# SenseLora_Soil_Moisture_V1_0.net
KiCad netlist of a schematic drawn in EAGLE
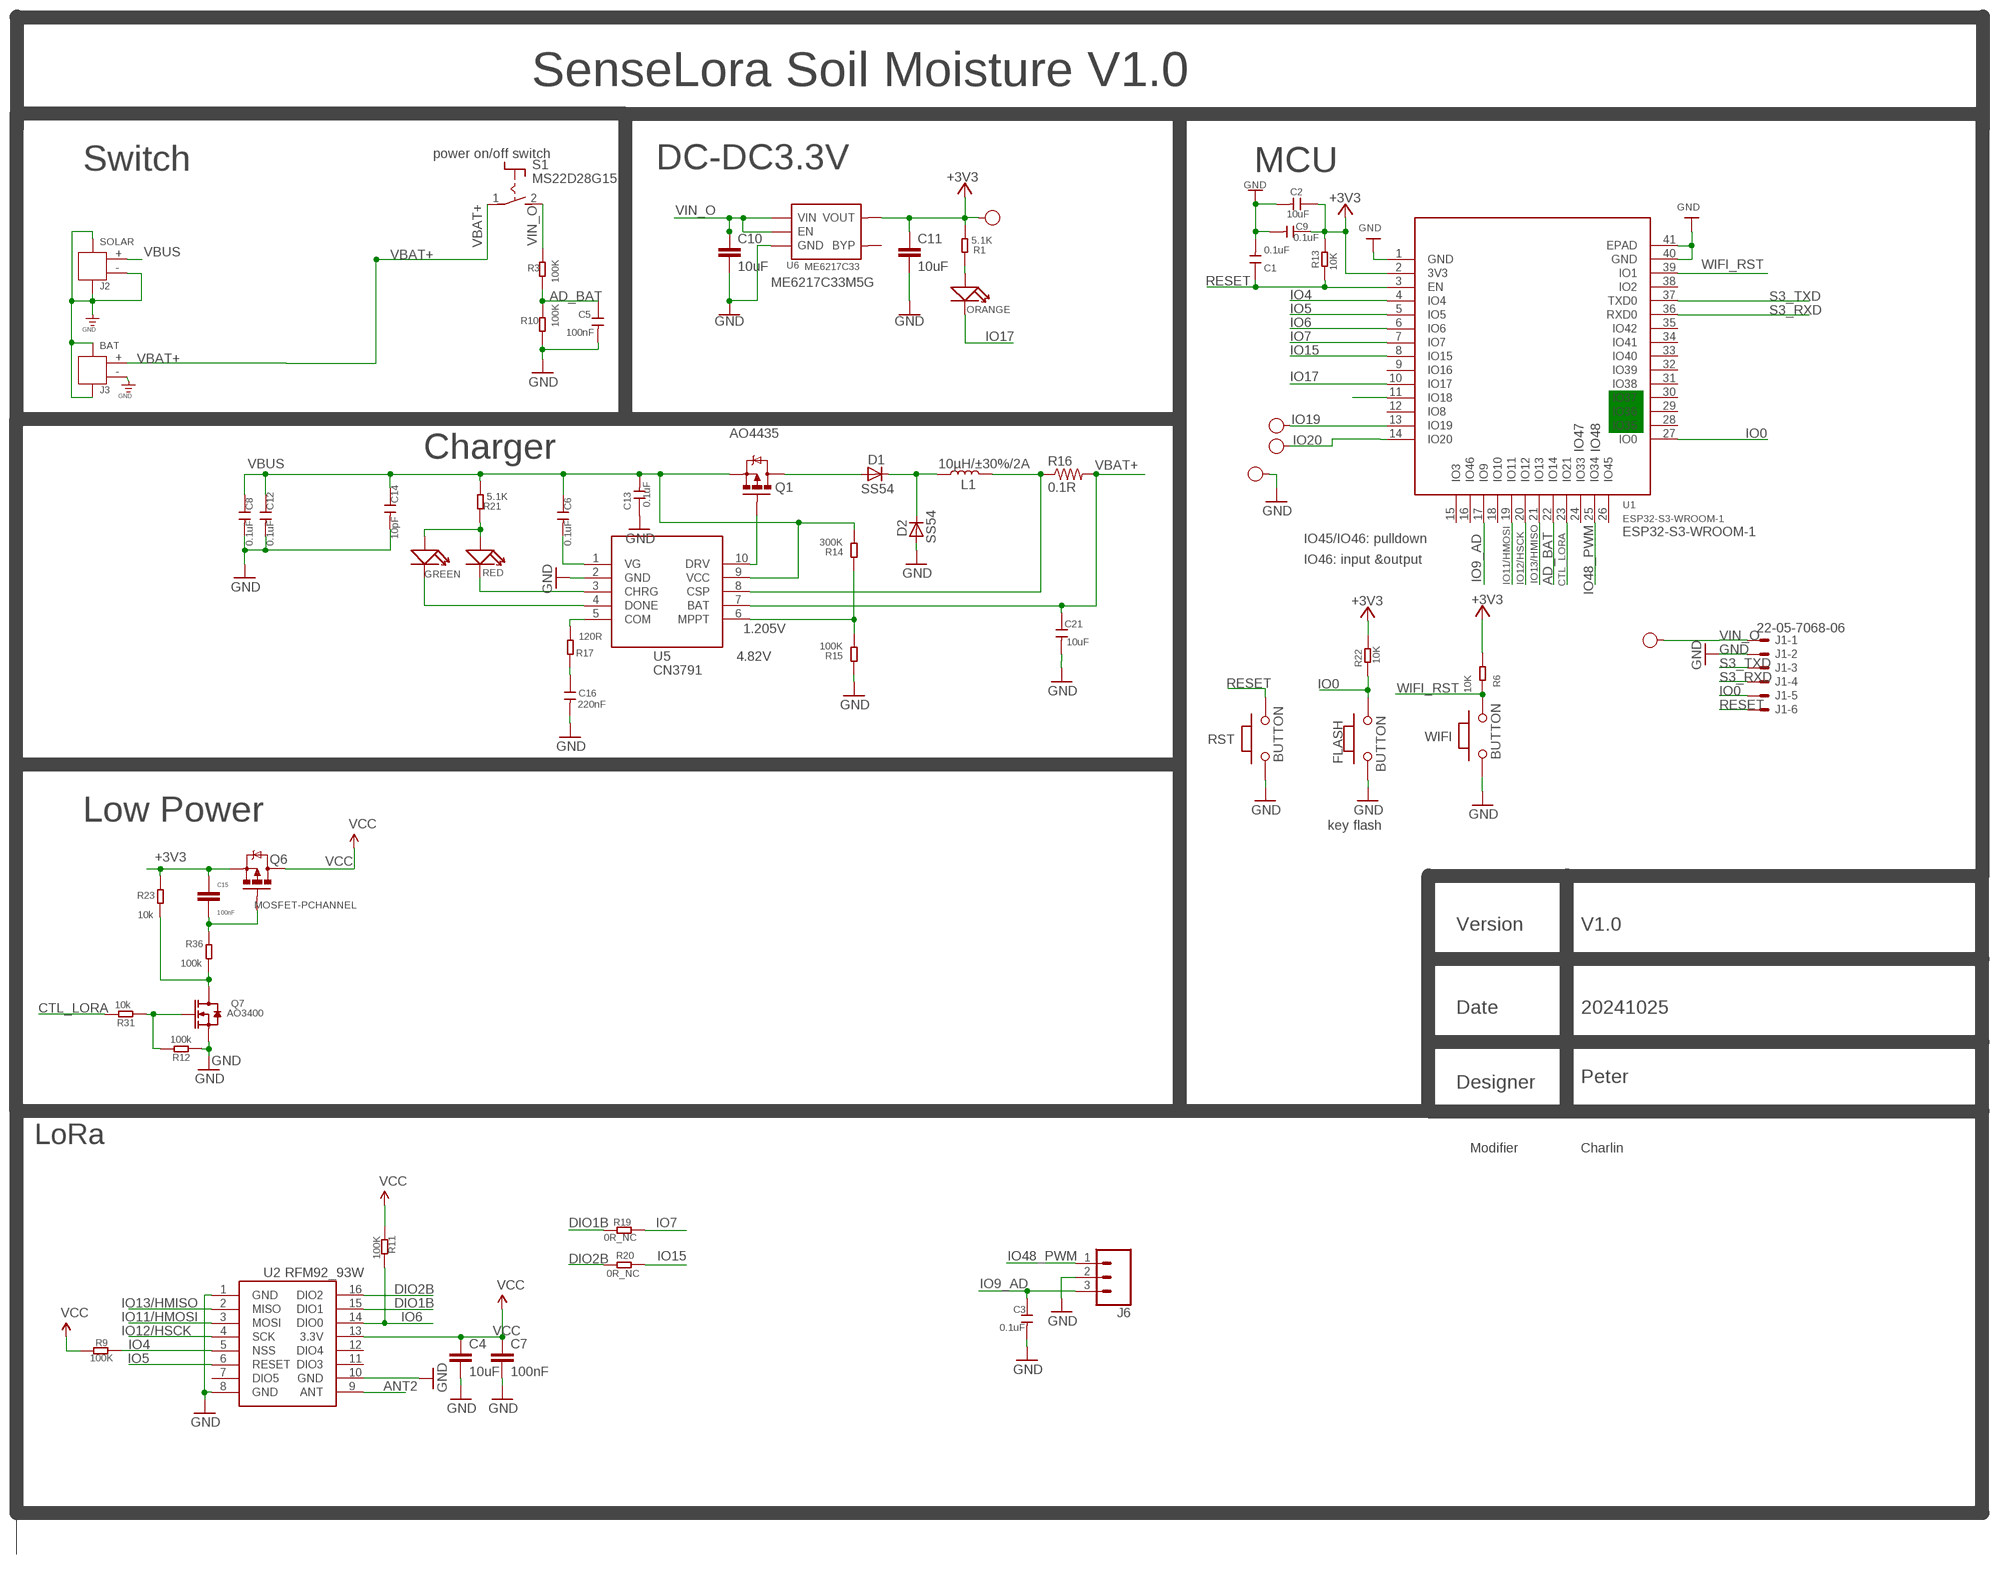
[diagram p0: schematic, sheet 1]

(export (version "E")
  (design (tool "Eeschema 10.0.6"))
  (components
    (comp (ref "3V3")
      (value "TEST-POINT'4545'")
      (footprint "eagle-import:TP-D45MIL")
      (fields (field (name "PARTNO") "DNP") (field (name "PARTNO_1") "DNP"))
      (libsource (lib "eagle-import") (part "TEST-POINT'4545'"))
    )
    (comp (ref "C1")
      (value "0.1uF")
      (footprint "eagle-import:DISCRETE_C0603")
      (libsource (lib "eagle-import") (part "DISCRETE_C-0603"))
    )
    (comp (ref "C2")
      (value "10uF")
      (footprint "eagle-import:DISCRETE_C0603")
      (libsource (lib "eagle-import") (part "DISCRETE_C-0603"))
    )
    (comp (ref "C3")
      (value "0.1uF")
      (footprint "eagle-import:DISCRETE_C0603")
      (libsource (lib "eagle-import") (part "DISCRETE_C-0603"))
    )
    (comp (ref "C4")
      (value "10uF")
      (footprint "eagle-import:C0603")
      (libsource (lib "eagle-import") (part "C0603"))
    )
    (comp (ref "C5")
      (value "100nF")
      (footprint "eagle-import:C0603")
      (libsource (lib "eagle-import") (part "CAP-0603"))
    )
    (comp (ref "C6")
      (value "0.1uF")
      (footprint "eagle-import:DISCRETE_C0603")
      (libsource (lib "eagle-import") (part "DISCRETE_C-0603"))
    )
    (comp (ref "C7")
      (value "100nF")
      (footprint "eagle-import:C0603")
      (libsource (lib "eagle-import") (part "C0603"))
    )
    (comp (ref "C8")
      (value "0.1uF")
      (footprint "eagle-import:DISCRETE_C0603")
      (libsource (lib "eagle-import") (part "DISCRETE_C-0603"))
    )
    (comp (ref "C9")
      (value "0.1uF")
      (footprint "eagle-import:DISCRETE_C0603")
      (libsource (lib "eagle-import") (part "DISCRETE_C-0603"))
    )
    (comp (ref "C10")
      (value "10uF")
      (footprint "eagle-import:C0603")
      (libsource (lib "eagle-import") (part "C0603"))
    )
    (comp (ref "C11")
      (value "10uF")
      (footprint "eagle-import:C0603")
      (libsource (lib "eagle-import") (part "C0603"))
    )
    (comp (ref "C12")
      (value "0.1uF")
      (footprint "eagle-import:DISCRETE_C0603")
      (libsource (lib "eagle-import") (part "DISCRETE_C-0603"))
    )
    (comp (ref "C13")
      (value "0.1uF")
      (footprint "eagle-import:DISCRETE_C0603")
      (libsource (lib "eagle-import") (part "DISCRETE_C-0603"))
    )
    (comp (ref "C14")
      (value "10pF")
      (footprint "eagle-import:DISCRETE_C0603")
      (libsource (lib "eagle-import") (part "DISCRETE_C-0603"))
    )
    (comp (ref "C15")
      (value "100nF")
      (footprint "eagle-import:C0603")
      (libsource (lib "eagle-import") (part "C0603"))
    )
    (comp (ref "C16")
      (value "220nF")
      (footprint "eagle-import:DISCRETE_C0603")
      (libsource (lib "eagle-import") (part "DISCRETE_C-0603"))
    )
    (comp (ref "C21")
      (value "10uF")
      (footprint "eagle-import:DISCRETE_C0603")
      (libsource (lib "eagle-import") (part "DISCRETE_C-0603"))
    )
    (comp (ref "CHRG")
      (value "RED")
      (footprint "eagle-import:LED-0603")
      (libsource (lib "eagle-import") (part "LED'0603'"))
    )
    (comp (ref "D+")
      (value "TEST-POINT'4545'")
      (footprint "eagle-import:TP-D45MIL")
      (fields (field (name "PARTNO") "DNP") (field (name "PARTNO_1") "DNP"))
      (libsource (lib "eagle-import") (part "TEST-POINT'4545'"))
    )
    (comp (ref "D-")
      (value "TEST-POINT'4545'")
      (footprint "eagle-import:TP-D45MIL")
      (fields (field (name "PARTNO") "DNP") (field (name "PARTNO_1") "DNP"))
      (libsource (lib "eagle-import") (part "TEST-POINT'4545'"))
    )
    (comp (ref "D1")
      (value "SS54")
      (footprint "eagle-import:DO-214AC")
      (libsource (lib "eagle-import") (part "DIODE-DO-214AC"))
    )
    (comp (ref "D2")
      (value "SS54")
      (footprint "eagle-import:DO-214AC")
      (libsource (lib "eagle-import") (part "DIODE-DO-214AC"))
    )
    (comp (ref "DONE")
      (value "GREEN")
      (footprint "eagle-import:LED-0603")
      (libsource (lib "eagle-import") (part "LED'0603'"))
    )
    (comp (ref "FLASH")
      (value "BUTTON")
      (footprint "eagle-import:157SW")
      (libsource (lib "eagle-import") (part "PB157"))
    )
    (comp (ref "GND")
      (value "TEST-POINT'4545'")
      (footprint "eagle-import:TP-D45MIL")
      (fields (field (name "PARTNO") "DNP") (field (name "PARTNO_1") "DNP"))
      (libsource (lib "eagle-import") (part "TEST-POINT'4545'"))
    )
    (comp (ref "J1")
      (value "22-05-7068-06")
      (footprint "eagle-import:7395-06")
      (libsource (lib "eagle-import") (part "22-?-0605-7068"))
    )
    (comp (ref "J2")
      (value "SOLAR")
      (footprint "eagle-import:HW2-SMD-2.0-90D")
      (libsource (lib "eagle-import") (part "JST-2P-SMD'2.0'"))
    )
    (comp (ref "J3")
      (value "BAT")
      (footprint "eagle-import:HW2-SMD-2.0-90D")
      (libsource (lib "eagle-import") (part "JST-2P-SMD'2.0'"))
    )
    (comp (ref "J6")
      (value "CONN_03SCREW")
      (footprint "eagle-import:SCREWTERMINAL-3.5MM-3")
      (libsource (lib "eagle-import") (part "CONN_03SCREW"))
    )
    (comp (ref "L1")
      (value "10µH/±30%/2A")
      (footprint "eagle-import:CR54")
      (fields (field (name "PROD_ID") "NDUC-11157"))
      (libsource (lib "eagle-import") (part "INDUCTOR-CR54-3.3UH"))
    )
    (comp (ref "Q1")
      (value "MOSFET-PCHANNELFDS6675")
      (footprint "eagle-import:SO08")
      (libsource (lib "eagle-import") (part "MOSFET-PCHANNELFDS6675"))
    )
    (comp (ref "Q6")
      (value "MOSFET-PCHANNEL")
      (footprint "eagle-import:SOT23-3")
      (fields (field (name "PROD_ID") "TRANS-08285"))
      (libsource (lib "eagle-import") (part "MOSFET-PCHANNEL"))
    )
    (comp (ref "Q7")
      (value "AO3400")
      (footprint "eagle-import:SOT23@1")
      (libsource (lib "eagle-import") (part "MOSFET-N'SOT23'"))
    )
    (comp (ref "R1")
      (value "5.1K")
      (footprint "eagle-import:DISCRETE_R0603")
      (libsource (lib "eagle-import") (part "DISCRETE_R-0603"))
    )
    (comp (ref "R3")
      (value "100K")
      (footprint "eagle-import:R0603")
      (libsource (lib "eagle-import") (part "R-0603"))
    )
    (comp (ref "R6")
      (value "10K")
      (footprint "eagle-import:R0603")
      (libsource (lib "eagle-import") (part "R-0603"))
    )
    (comp (ref "R9")
      (value "100K")
      (footprint "eagle-import:R0603")
      (libsource (lib "eagle-import") (part "R-0603"))
    )
    (comp (ref "R10")
      (value "100K")
      (footprint "eagle-import:R0603")
      (libsource (lib "eagle-import") (part "R-0603"))
    )
    (comp (ref "R11")
      (value "100K")
      (footprint "eagle-import:R0603")
      (libsource (lib "eagle-import") (part "R-0603"))
    )
    (comp (ref "R12")
      (value "100k")
      (footprint "eagle-import:R0603")
      (libsource (lib "eagle-import") (part "R-0603"))
    )
    (comp (ref "R13")
      (value "10K")
      (footprint "eagle-import:R0603")
      (libsource (lib "eagle-import") (part "R-0603"))
    )
    (comp (ref "R14")
      (value "300K")
      (footprint "eagle-import:DISCRETE_R0603")
      (libsource (lib "eagle-import") (part "DISCRETE_R-0603"))
    )
    (comp (ref "R15")
      (value "100K")
      (footprint "eagle-import:DISCRETE_R0603")
      (libsource (lib "eagle-import") (part "DISCRETE_R-0603"))
    )
    (comp (ref "R16")
      (value "0.1R")
      (footprint "eagle-import:R1206")
      (libsource (lib "eagle-import") (part "R-US_R1206"))
    )
    (comp (ref "R17")
      (value "120R")
      (footprint "eagle-import:DISCRETE_R0603")
      (libsource (lib "eagle-import") (part "DISCRETE_R-0603"))
    )
    (comp (ref "R19")
      (value "0R_NC")
      (footprint "eagle-import:R0603")
      (libsource (lib "eagle-import") (part "R-0603"))
    )
    (comp (ref "R20")
      (value "0R_NC")
      (footprint "eagle-import:R0603")
      (libsource (lib "eagle-import") (part "R-0603"))
    )
    (comp (ref "R21")
      (value "5.1K")
      (footprint "eagle-import:DISCRETE_R0603")
      (libsource (lib "eagle-import") (part "DISCRETE_R-0603"))
    )
    (comp (ref "R22")
      (value "10K")
      (footprint "eagle-import:R0603")
      (libsource (lib "eagle-import") (part "R-0603"))
    )
    (comp (ref "R23")
      (value "10k")
      (footprint "eagle-import:R0603")
      (libsource (lib "eagle-import") (part "R-0603"))
    )
    (comp (ref "R31")
      (value "10k")
      (footprint "eagle-import:R0603")
      (libsource (lib "eagle-import") (part "R-0603"))
    )
    (comp (ref "R36")
      (value "100k")
      (footprint "eagle-import:R0603")
      (libsource (lib "eagle-import") (part "R-0603"))
    )
    (comp (ref "RST")
      (value "BUTTON")
      (footprint "eagle-import:157SW")
      (libsource (lib "eagle-import") (part "PB157"))
    )
    (comp (ref "S1")
      (value "MS22D28G15")
      (footprint "eagle-import:S-MS22D28G15")
      (libsource (lib "eagle-import") (part "MS22D28G15"))
    )
    (comp (ref "STA")
      (value "ORANGE")
      (footprint "eagle-import:LED-0603")
      (libsource (lib "eagle-import") (part "LED'0603'"))
    )
    (comp (ref "U1")
      (value "ESP32-S3-WROOM-1")
      (footprint "eagle-import:ESP32-­S2-­SOLO")
      (libsource (lib "eagle-import") (part "ESP32­S2­SOLO"))
    )
    (comp (ref "U2")
      (value "RFM92_93W")
      (footprint "eagle-import:RFM92_93W")
      (libsource (lib "eagle-import") (part "RFM92_93W"))
    )
    (comp (ref "U5")
      (value "CN3791")
      (footprint "eagle-import:SSOP-10-150MIL")
      (libsource (lib "eagle-import") (part "CN3791"))
    )
    (comp (ref "U6")
      (value "ME6217C33")
      (footprint "eagle-import:SOT23-5")
      (libsource (lib "eagle-import") (part "SPX3819"))
    )
    (comp (ref "VI")
      (value "HP")
      (footprint "eagle-import:TP-D45MIL")
      (fields (field (name "PARTNO") "DNP") (field (name "PARTNO_1") "DNP"))
      (libsource (lib "eagle-import") (part "TEST-POINT'4545'"))
    )
    (comp (ref "WIFI")
      (value "BUTTON")
      (footprint "eagle-import:157SW")
      (libsource (lib "eagle-import") (part "PB157"))
    )
  )
  (nets
    (net (code "1") (name "+3V3") (class "Default")
      (node (ref "3V3") (pin "T") (pinfunction "T_T") (pintype "bidirectional"))
      (node (ref "C11") (pin "1") (pinfunction "1_1") (pintype "passive"))
      (node (ref "C15") (pin "1") (pinfunction "1_1") (pintype "passive"))
      (node (ref "C2") (pin "1") (pinfunction "1_1") (pintype "passive"))
      (node (ref "C9") (pin "1") (pinfunction "1_1") (pintype "passive"))
      (node (ref "Q6") (pin "2") (pinfunction "S_2") (pintype "passive"))
      (node (ref "R1") (pin "2") (pinfunction "2_2") (pintype "passive"))
      (node (ref "R13") (pin "2") (pinfunction "2_2") (pintype "passive"))
      (node (ref "R22") (pin "2") (pinfunction "2_2") (pintype "passive"))
      (node (ref "R23") (pin "2") (pinfunction "2_2") (pintype "passive"))
      (node (ref "R6") (pin "2") (pinfunction "2_2") (pintype "passive"))
      (node (ref "U1") (pin "2") (pinfunction "3V3_2") (pintype "bidirectional"))
      (node (ref "U6") (pin "5") (pinfunction "VOUT_5") (pintype "bidirectional"))
    )
    (net (code "2") (name "/AD_BAT") (class "Default")
      (node (ref "C5") (pin "1") (pinfunction "1_1") (pintype "passive"))
      (node (ref "R10") (pin "1") (pinfunction "1_1") (pintype "passive"))
      (node (ref "R3") (pin "2") (pinfunction "2_2") (pintype "passive"))
      (node (ref "U1") (pin "22") (pinfunction "IO14_22") (pintype "bidirectional"))
    )
    (net (code "3") (name "/ANT2") (class "Default")
      (node (ref "U2") (pin "9") (pinfunction "ANT_9") (pintype "bidirectional"))
    )
    (net (code "4") (name "/CTL_LORA") (class "Default")
      (node (ref "R31") (pin "2") (pinfunction "2_2") (pintype "passive"))
      (node (ref "U1") (pin "23") (pinfunction "IO21_23") (pintype "bidirectional"))
    )
    (net (code "5") (name "/DIO1B") (class "Default")
      (node (ref "R19") (pin "2") (pinfunction "2_2") (pintype "passive"))
      (node (ref "U2") (pin "15") (pinfunction "DIO1_15") (pintype "bidirectional"))
    )
    (net (code "6") (name "/DIO2B") (class "Default")
      (node (ref "R20") (pin "2") (pinfunction "2_2") (pintype "passive"))
      (node (ref "U2") (pin "16") (pinfunction "DIO2_16") (pintype "bidirectional"))
    )
    (net (code "7") (name "/IO0") (class "Default")
      (node (ref "FLASH") (pin "2") (pinfunction "2_2") (pintype "passive"))
      (node (ref "J1") (pin "5") (pinfunction "S_5") (pintype "passive"))
      (node (ref "R22") (pin "1") (pinfunction "1_1") (pintype "passive"))
      (node (ref "U1") (pin "27") (pinfunction "IO0_27") (pintype "bidirectional"))
    )
    (net (code "8") (name "/IO4") (class "Default")
      (node (ref "R9") (pin "1") (pinfunction "1_1") (pintype "passive"))
      (node (ref "U1") (pin "4") (pinfunction "IO4_4") (pintype "bidirectional"))
      (node (ref "U2") (pin "5") (pinfunction "NSS_5") (pintype "bidirectional"))
    )
    (net (code "9") (name "/IO5") (class "Default")
      (node (ref "U1") (pin "5") (pinfunction "IO5_5") (pintype "bidirectional"))
      (node (ref "U2") (pin "6") (pinfunction "RESET_6") (pintype "bidirectional"))
    )
    (net (code "10") (name "/IO6") (class "Default")
      (node (ref "R11") (pin "1") (pinfunction "1_1") (pintype "passive"))
      (node (ref "U1") (pin "6") (pinfunction "IO6_6") (pintype "bidirectional"))
      (node (ref "U2") (pin "14") (pinfunction "DIO0_14") (pintype "bidirectional"))
    )
    (net (code "11") (name "/IO7") (class "Default")
      (node (ref "R19") (pin "1") (pinfunction "1_1") (pintype "passive"))
      (node (ref "U1") (pin "7") (pinfunction "IO7_7") (pintype "bidirectional"))
    )
    (net (code "12") (name "/IO9_AD") (class "Default")
      (node (ref "C3") (pin "1") (pinfunction "1_1") (pintype "passive"))
      (node (ref "J6") (pin "3") (pinfunction "3_3") (pintype "passive"))
      (node (ref "U1") (pin "17") (pinfunction "IO9_17") (pintype "bidirectional"))
    )
    (net (code "13") (name "/IO11{slash}HMOSI") (class "Default")
      (node (ref "U1") (pin "19") (pinfunction "IO11_19") (pintype "bidirectional"))
      (node (ref "U2") (pin "3") (pinfunction "MOSI_3") (pintype "bidirectional"))
    )
    (net (code "14") (name "/IO12{slash}HSCK") (class "Default")
      (node (ref "U1") (pin "20") (pinfunction "IO12_20") (pintype "bidirectional"))
      (node (ref "U2") (pin "4") (pinfunction "SCK_4") (pintype "bidirectional"))
    )
    (net (code "15") (name "/IO13{slash}HMISO") (class "Default")
      (node (ref "U1") (pin "21") (pinfunction "IO13_21") (pintype "bidirectional"))
      (node (ref "U2") (pin "2") (pinfunction "MISO_2") (pintype "bidirectional"))
    )
    (net (code "16") (name "/IO15") (class "Default")
      (node (ref "R20") (pin "1") (pinfunction "1_1") (pintype "passive"))
      (node (ref "U1") (pin "8") (pinfunction "IO15_8") (pintype "bidirectional"))
    )
    (net (code "17") (name "/IO17") (class "Default")
      (node (ref "STA") (pin "-") (pinfunction "-_-") (pintype "passive"))
      (node (ref "U1") (pin "10") (pinfunction "IO17_10") (pintype "bidirectional"))
    )
    (net (code "18") (name "/IO19") (class "Default")
      (node (ref "D-") (pin "T") (pinfunction "T_T") (pintype "bidirectional"))
      (node (ref "U1") (pin "13") (pinfunction "IO19_13") (pintype "bidirectional"))
    )
    (net (code "19") (name "/IO20") (class "Default")
      (node (ref "D+") (pin "T") (pinfunction "T_T") (pintype "bidirectional"))
      (node (ref "U1") (pin "14") (pinfunction "IO20_14") (pintype "bidirectional"))
    )
    (net (code "20") (name "/IO48_PWM") (class "Default")
      (node (ref "J6") (pin "1") (pinfunction "1_1") (pintype "passive"))
      (node (ref "U1") (pin "25") (pinfunction "IO34_25") (pintype "bidirectional"))
    )
    (net (code "21") (name "/RESET") (class "Default")
      (node (ref "C1") (pin "1") (pinfunction "1_1") (pintype "passive"))
      (node (ref "J1") (pin "6") (pinfunction "S_6") (pintype "passive"))
      (node (ref "R13") (pin "1") (pinfunction "1_1") (pintype "passive"))
      (node (ref "RST") (pin "2") (pinfunction "2_2") (pintype "passive"))
      (node (ref "U1") (pin "3") (pinfunction "EN_3") (pintype "bidirectional"))
    )
    (net (code "22") (name "/S3_RXD") (class "Default")
      (node (ref "J1") (pin "4") (pinfunction "S_4") (pintype "passive"))
      (node (ref "U1") (pin "36") (pinfunction "RXD0_36") (pintype "bidirectional"))
    )
    (net (code "23") (name "/S3_TXD") (class "Default")
      (node (ref "J1") (pin "3") (pinfunction "S_3") (pintype "passive"))
      (node (ref "U1") (pin "37") (pinfunction "TXD0_37") (pintype "bidirectional"))
    )
    (net (code "24") (name "/VBAT+") (class "Default")
      (node (ref "C21") (pin "1") (pinfunction "1_1") (pintype "passive"))
      (node (ref "J3") (pin "+") (pinfunction "1_+") (pintype "bidirectional"))
      (node (ref "R16") (pin "2") (pinfunction "2_2") (pintype "passive"))
      (node (ref "S1") (pin "1") (pinfunction "P_1") (pintype "passive"))
      (node (ref "U5") (pin "7") (pinfunction "BAT_7") (pintype "bidirectional"))
    )
    (net (code "25") (name "/VBUS") (class "Default")
      (node (ref "C12") (pin "1") (pinfunction "1_1") (pintype "passive"))
      (node (ref "C13") (pin "2") (pinfunction "2_2") (pintype "passive"))
      (node (ref "C14") (pin "1") (pinfunction "1_1") (pintype "passive"))
      (node (ref "C6") (pin "1") (pinfunction "1_1") (pintype "passive"))
      (node (ref "C8") (pin "1") (pinfunction "1_1") (pintype "passive"))
      (node (ref "J2") (pin "+") (pinfunction "1_+") (pintype "bidirectional"))
      (node (ref "Q1") (pin "1") (pinfunction "S_1") (pintype "passive"))
      (node (ref "Q1") (pin "2") (pinfunction "S_2") (pintype "passive"))
      (node (ref "Q1") (pin "3") (pinfunction "S_3") (pintype "passive"))
      (node (ref "R14") (pin "2") (pinfunction "2_2") (pintype "passive"))
      (node (ref "R21") (pin "2") (pinfunction "2_2") (pintype "passive"))
      (node (ref "U5") (pin "9") (pinfunction "VCC_9") (pintype "bidirectional"))
    )
    (net (code "26") (name "/VIN_O") (class "Default")
      (node (ref "C10") (pin "1") (pinfunction "1_1") (pintype "passive"))
      (node (ref "J1") (pin "1") (pinfunction "S_1") (pintype "passive"))
      (node (ref "R3") (pin "1") (pinfunction "1_1") (pintype "passive"))
      (node (ref "S1") (pin "2") (pinfunction "S_2") (pintype "passive"))
      (node (ref "U6") (pin "1") (pinfunction "VIN_1") (pintype "bidirectional"))
      (node (ref "U6") (pin "3") (pinfunction "EN_3") (pintype "bidirectional"))
      (node (ref "VI") (pin "T") (pinfunction "T_T") (pintype "bidirectional"))
    )
    (net (code "27") (name "/WIFI_RST") (class "Default")
      (node (ref "R6") (pin "1") (pinfunction "1_1") (pintype "passive"))
      (node (ref "U1") (pin "39") (pinfunction "IO1_39") (pintype "bidirectional"))
      (node (ref "WIFI") (pin "2") (pinfunction "2_2") (pintype "passive"))
    )
    (net (code "28") (name "GND") (class "Default")
      (node (ref "C1") (pin "2") (pinfunction "2_2") (pintype "passive"))
      (node (ref "C10") (pin "2") (pinfunction "2_2") (pintype "passive"))
      (node (ref "C11") (pin "2") (pinfunction "2_2") (pintype "passive"))
      (node (ref "C12") (pin "2") (pinfunction "2_2") (pintype "passive"))
      (node (ref "C13") (pin "1") (pinfunction "1_1") (pintype "passive"))
      (node (ref "C14") (pin "2") (pinfunction "2_2") (pintype "passive"))
      (node (ref "C16") (pin "2") (pinfunction "2_2") (pintype "passive"))
      (node (ref "C2") (pin "2") (pinfunction "2_2") (pintype "passive"))
      (node (ref "C21") (pin "2") (pinfunction "2_2") (pintype "passive"))
      (node (ref "C3") (pin "2") (pinfunction "2_2") (pintype "passive"))
      (node (ref "C4") (pin "2") (pinfunction "2_2") (pintype "passive"))
      (node (ref "C5") (pin "2") (pinfunction "2_2") (pintype "passive"))
      (node (ref "C7") (pin "2") (pinfunction "2_2") (pintype "passive"))
      (node (ref "C8") (pin "2") (pinfunction "2_2") (pintype "passive"))
      (node (ref "C9") (pin "2") (pinfunction "2_2") (pintype "passive"))
      (node (ref "D2") (pin "A") (pinfunction "A_A") (pintype "passive"))
      (node (ref "FLASH") (pin "1") (pinfunction "1_1") (pintype "passive"))
      (node (ref "GND") (pin "T") (pinfunction "T_T") (pintype "bidirectional"))
      (node (ref "J1") (pin "2") (pinfunction "S_2") (pintype "passive"))
      (node (ref "J2") (pin "-") (pinfunction "2_-") (pintype "bidirectional"))
      (node (ref "J2") (pin "3") (pinfunction "3_3") (pintype "bidirectional"))
      (node (ref "J2") (pin "4") (pinfunction "4_4") (pintype "bidirectional"))
      (node (ref "J3") (pin "-") (pinfunction "2_-") (pintype "bidirectional"))
      (node (ref "J3") (pin "3") (pinfunction "3_3") (pintype "bidirectional"))
      (node (ref "J3") (pin "4") (pinfunction "4_4") (pintype "bidirectional"))
      (node (ref "J6") (pin "2") (pinfunction "2_2") (pintype "passive"))
      (node (ref "Q7") (pin "2") (pinfunction "S_2") (pintype "passive"))
      (node (ref "R10") (pin "2") (pinfunction "2_2") (pintype "passive"))
      (node (ref "R12") (pin "1") (pinfunction "1_1") (pintype "passive"))
      (node (ref "R15") (pin "1") (pinfunction "1_1") (pintype "passive"))
      (node (ref "RST") (pin "1") (pinfunction "1_1") (pintype "passive"))
      (node (ref "U1") (pin "1") (pinfunction "GND_1") (pintype "bidirectional"))
      (node (ref "U1") (pin "40") (pinfunction "GND_40") (pintype "bidirectional"))
      (node (ref "U1") (pin "41") (pinfunction "EPAD_41") (pintype "bidirectional"))
      (node (ref "U2") (pin "1") (pinfunction "GND_1") (pintype "power_in"))
      (node (ref "U2") (pin "10") (pinfunction "GND_10") (pintype "power_in"))
      (node (ref "U2") (pin "8") (pinfunction "GND_8") (pintype "power_in"))
      (node (ref "U5") (pin "2") (pinfunction "GND_2") (pintype "bidirectional"))
      (node (ref "U6") (pin "2") (pinfunction "GND_2") (pintype "bidirectional"))
      (node (ref "WIFI") (pin "1") (pinfunction "1_1") (pintype "passive"))
    )
    (net (code "29") (name "Net-(C16-Pad1)") (class "Default")
      (node (ref "C16") (pin "1") (pinfunction "1_1") (pintype "passive"))
      (node (ref "R17") (pin "1") (pinfunction "1_1") (pintype "passive"))
    )
    (net (code "30") (name "Net-(CHRG-Pad+)") (class "Default")
      (node (ref "CHRG") (pin "+") (pinfunction "+_+") (pintype "passive"))
      (node (ref "DONE") (pin "+") (pinfunction "+_+") (pintype "passive"))
      (node (ref "R21") (pin "1") (pinfunction "1_1") (pintype "passive"))
    )
    (net (code "31") (name "Net-(D1-PadA)") (class "Default")
      (node (ref "D1") (pin "A") (pinfunction "A_A") (pintype "passive"))
      (node (ref "Q1") (pin "5") (pinfunction "D_5") (pintype "passive"))
      (node (ref "Q1") (pin "6") (pinfunction "D_6") (pintype "passive"))
      (node (ref "Q1") (pin "7") (pinfunction "D_7") (pintype "passive"))
      (node (ref "Q1") (pin "8") (pinfunction "D_8") (pintype "passive"))
    )
    (net (code "32") (name "Net-(L1-1)") (class "Default")
      (node (ref "D1") (pin "C") (pinfunction "C_C") (pintype "passive"))
      (node (ref "D2") (pin "C") (pinfunction "C_C") (pintype "passive"))
      (node (ref "L1") (pin "P$1") (pinfunction "1_P$1") (pintype "passive"))
    )
    (net (code "33") (name "Net-(L1-2)") (class "Default")
      (node (ref "L1") (pin "P$2") (pinfunction "2_P$2") (pintype "passive"))
      (node (ref "R16") (pin "1") (pinfunction "1_1") (pintype "passive"))
      (node (ref "U5") (pin "8") (pinfunction "CSP_8") (pintype "bidirectional"))
    )
    (net (code "34") (name "Net-(Q1-G)") (class "Default")
      (node (ref "Q1") (pin "4") (pinfunction "G_4") (pintype "passive"))
      (node (ref "U5") (pin "10") (pinfunction "DRV_10") (pintype "bidirectional"))
    )
    (net (code "35") (name "Net-(Q6-G)") (class "Default")
      (node (ref "C15") (pin "2") (pinfunction "2_2") (pintype "passive"))
      (node (ref "Q6") (pin "1") (pinfunction "G_1") (pintype "passive"))
      (node (ref "R36") (pin "2") (pinfunction "2_2") (pintype "passive"))
    )
    (net (code "36") (name "Net-(Q7-D)") (class "Default")
      (node (ref "Q7") (pin "3") (pinfunction "D_3") (pintype "passive"))
      (node (ref "R23") (pin "1") (pinfunction "1_1") (pintype "passive"))
      (node (ref "R36") (pin "1") (pinfunction "1_1") (pintype "passive"))
    )
    (net (code "37") (name "Net-(Q7-G)") (class "Default")
      (node (ref "Q7") (pin "1") (pinfunction "G_1") (pintype "passive"))
      (node (ref "R12") (pin "2") (pinfunction "2_2") (pintype "passive"))
      (node (ref "R31") (pin "1") (pinfunction "1_1") (pintype "passive"))
    )
    (net (code "38") (name "Net-(R1-Pad1)") (class "Default")
      (node (ref "R1") (pin "1") (pinfunction "1_1") (pintype "passive"))
      (node (ref "STA") (pin "+") (pinfunction "+_+") (pintype "passive"))
    )
    (net (code "39") (name "Net-(U5-CHRG)") (class "Default")
      (node (ref "CHRG") (pin "-") (pinfunction "-_-") (pintype "passive"))
      (node (ref "U5") (pin "3") (pinfunction "CHRG_3") (pintype "bidirectional"))
    )
    (net (code "40") (name "Net-(U5-COM)") (class "Default")
      (node (ref "R17") (pin "2") (pinfunction "2_2") (pintype "passive"))
      (node (ref "U5") (pin "5") (pinfunction "COM_5") (pintype "bidirectional"))
    )
    (net (code "41") (name "Net-(U5-DONE)") (class "Default")
      (node (ref "DONE") (pin "-") (pinfunction "-_-") (pintype "passive"))
      (node (ref "U5") (pin "4") (pinfunction "DONE_4") (pintype "bidirectional"))
    )
    (net (code "42") (name "Net-(U5-MPPT)") (class "Default")
      (node (ref "R14") (pin "1") (pinfunction "1_1") (pintype "passive"))
      (node (ref "R15") (pin "2") (pinfunction "2_2") (pintype "passive"))
      (node (ref "U5") (pin "6") (pinfunction "MPPT_6") (pintype "bidirectional"))
    )
    (net (code "43") (name "Net-(U5-VG)") (class "Default")
      (node (ref "C6") (pin "2") (pinfunction "2_2") (pintype "passive"))
      (node (ref "U5") (pin "1") (pinfunction "VG_1") (pintype "bidirectional"))
    )
    (net (code "44") (name "VCC") (class "Default")
      (node (ref "C4") (pin "1") (pinfunction "1_1") (pintype "passive"))
      (node (ref "C7") (pin "1") (pinfunction "1_1") (pintype "passive"))
      (node (ref "Q6") (pin "3") (pinfunction "D_3") (pintype "passive"))
      (node (ref "R11") (pin "2") (pinfunction "2_2") (pintype "passive"))
      (node (ref "R9") (pin "2") (pinfunction "2_2") (pintype "passive"))
      (node (ref "U2") (pin "13") (pinfunction "3.3V_13") (pintype "power_in"))
    )
    (net (code "45") (name "unconnected-(U1-IO2-Pad38)") (class "Default")
      (node (ref "U1") (pin "38") (pinfunction "IO2_38") (pintype "bidirectional"))
    )
    (net (code "46") (name "unconnected-(U1-IO3-Pad15)") (class "Default")
      (node (ref "U1") (pin "15") (pinfunction "IO3_15") (pintype "bidirectional"))
    )
    (net (code "47") (name "unconnected-(U1-IO8-Pad12)") (class "Default")
      (node (ref "U1") (pin "12") (pinfunction "IO8_12") (pintype "bidirectional"))
    )
    (net (code "48") (name "unconnected-(U1-IO10-Pad18)") (class "Default")
      (node (ref "U1") (pin "18") (pinfunction "IO10_18") (pintype "bidirectional"))
    )
    (net (code "49") (name "unconnected-(U1-IO16-Pad9)") (class "Default")
      (node (ref "U1") (pin "9") (pinfunction "IO16_9") (pintype "bidirectional"))
    )
    (net (code "50") (name "unconnected-(U1-IO18-Pad11)") (class "Default")
      (node (ref "U1") (pin "11") (pinfunction "IO18_11") (pintype "bidirectional"))
    )
    (net (code "51") (name "unconnected-(U1-IO33-Pad24)") (class "Default")
      (node (ref "U1") (pin "24") (pinfunction "IO33_24") (pintype "bidirectional"))
    )
    (net (code "52") (name "unconnected-(U1-IO35-Pad28)") (class "Default")
      (node (ref "U1") (pin "28") (pinfunction "IO35_28") (pintype "bidirectional"))
    )
    (net (code "53") (name "unconnected-(U1-IO36-Pad29)") (class "Default")
      (node (ref "U1") (pin "29") (pinfunction "IO36_29") (pintype "bidirectional"))
    )
    (net (code "54") (name "unconnected-(U1-IO37-Pad30)") (class "Default")
      (node (ref "U1") (pin "30") (pinfunction "IO37_30") (pintype "bidirectional"))
    )
    (net (code "55") (name "unconnected-(U1-IO38-Pad31)") (class "Default")
      (node (ref "U1") (pin "31") (pinfunction "IO38_31") (pintype "bidirectional"))
    )
    (net (code "56") (name "unconnected-(U1-IO39-Pad32)") (class "Default")
      (node (ref "U1") (pin "32") (pinfunction "IO39_32") (pintype "bidirectional"))
    )
    (net (code "57") (name "unconnected-(U1-IO40-Pad33)") (class "Default")
      (node (ref "U1") (pin "33") (pinfunction "IO40_33") (pintype "bidirectional"))
    )
    (net (code "58") (name "unconnected-(U1-IO41-Pad34)") (class "Default")
      (node (ref "U1") (pin "34") (pinfunction "IO41_34") (pintype "bidirectional"))
    )
    (net (code "59") (name "unconnected-(U1-IO42-Pad35)") (class "Default")
      (node (ref "U1") (pin "35") (pinfunction "IO42_35") (pintype "bidirectional"))
    )
    (net (code "60") (name "unconnected-(U1-IO45-Pad26)") (class "Default")
      (node (ref "U1") (pin "26") (pinfunction "IO45_26") (pintype "bidirectional"))
    )
    (net (code "61") (name "unconnected-(U1-IO46-Pad16)") (class "Default")
      (node (ref "U1") (pin "16") (pinfunction "IO46_16") (pintype "bidirectional"))
    )
    (net (code "62") (name "unconnected-(U2-DIO3-Pad11)") (class "Default")
      (node (ref "U2") (pin "11") (pinfunction "DIO3_11") (pintype "bidirectional"))
    )
    (net (code "63") (name "unconnected-(U2-DIO4-Pad12)") (class "Default")
      (node (ref "U2") (pin "12") (pinfunction "DIO4_12") (pintype "bidirectional"))
    )
    (net (code "64") (name "unconnected-(U2-DIO5-Pad7)") (class "Default")
      (node (ref "U2") (pin "7") (pinfunction "DIO5_7") (pintype "bidirectional"))
    )
    (net (code "65") (name "unconnected-(U6-BYP-Pad4)") (class "Default")
      (node (ref "U6") (pin "4") (pinfunction "BYP_4") (pintype "bidirectional"))
    )
  )
)
